# main.net
KiCad netlist of a schematic drawn in Altium Designer
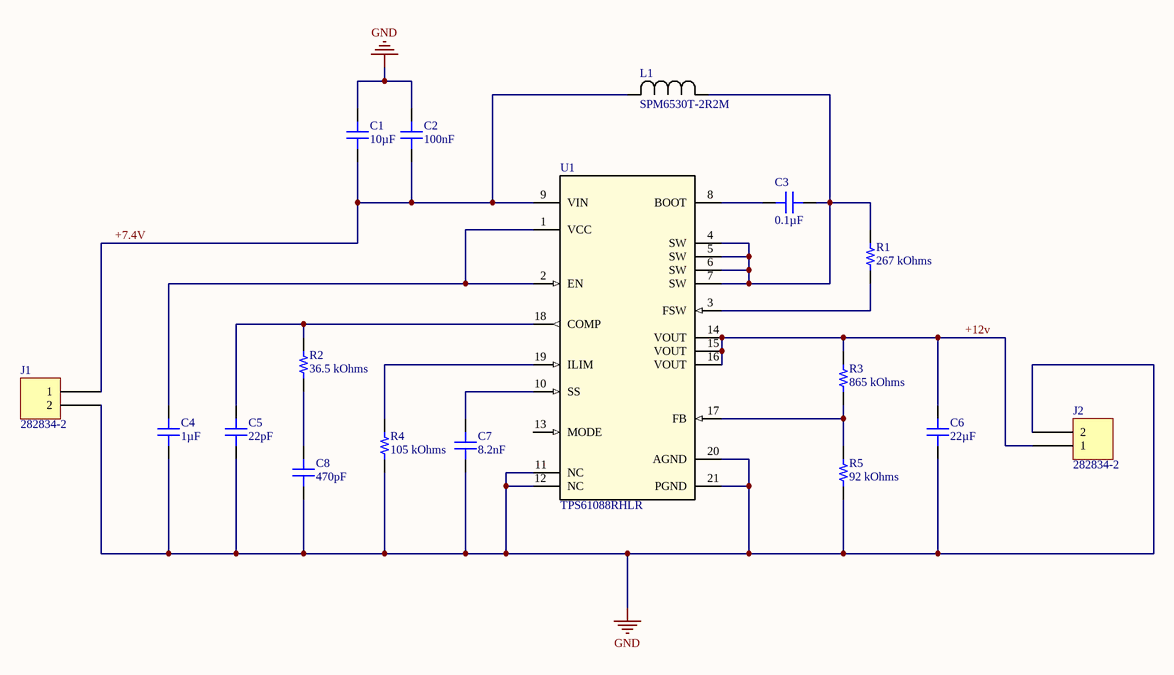
[diagram p0: main.SchDoc]

(export (version "E")
  (design (tool "Eeschema 10.0.6"))
  (components
    (comp (ref "C1")
      (value "10µF")
      (footprint "CAP 1210_3225 - 2.8MM")
      (description "CAP CER 10UF 50V X7S 1210")
      (fields
        (field (name "PART NUMBER") "GCJ32EC71H106KA01L")
        (field (name "MANUFACTURER") "Murata Electronics")
      )
      (libsource (lib "Celestial Altium Library - altium_library") (part "Capacitor"))
    )
    (comp (ref "C2")
      (value "100nF")
      (footprint "CAP 0603_1608")
      (description "CAP CER 22PF 25V C0G/NP0 0603")
      (fields (field (name "PART NUMBER") "06033A220KAT2A") (field (name "MANUFACTURER") "AVX Corporation"))
      (libsource (lib "Celestial Altium Library - altium_library") (part "Capacitor"))
    )
    (comp (ref "C3")
      (value "0.1µF")
      (footprint "CAP 0603_1608")
      (description "CAP CER 0.1UF 16V X7R 0603")
      (fields (field (name "PART NUMBER") "0603YC104JAT4A") (field (name "MANUFACTURER") "AVX Corporation"))
      (libsource (lib "Celestial Altium Library - altium_library") (part "Capacitor"))
    )
    (comp (ref "C4")
      (value "1µF")
      (footprint "CAP 0603_1608")
      (description "CAP CER 1UF 16V X5R 0603")
      (fields (field (name "PART NUMBER") "C0603C105K4PACTU") (field (name "MANUFACTURER") "KEMET"))
      (libsource (lib "Celestial Altium Library - altium_library") (part "Capacitor"))
    )
    (comp (ref "C5")
      (value "22pF")
      (footprint "CAP 0603_1608")
      (description "CAP CER 22PF 25V C0G/NP0 0603")
      (fields (field (name "PART NUMBER") "06033A220KAT2A") (field (name "MANUFACTURER") "AVX Corporation"))
      (libsource (lib "Celestial Altium Library - altium_library") (part "Capacitor"))
    )
    (comp (ref "C6")
      (value "22µF")
      (footprint "CAP 1210_3225 - 2.8MM")
      (description "CAP CER 22UF 25V X7R 1210")
      (fields
        (field (name "PART NUMBER") "GRM32ER71E226ME15K")
        (field (name "MANUFACTURER") "Murata Electronics")
      )
      (libsource (lib "Celestial Altium Library - altium_library") (part "Capacitor"))
    )
    (comp (ref "C7")
      (value "8.2nF")
      (footprint "CAP 0603_1608")
      (description "CAP CER 1UF 16V X5R 0603")
      (fields (field (name "PART NUMBER") "C0603C105K4PACTU") (field (name "MANUFACTURER") "KEMET"))
      (libsource (lib "Celestial Altium Library - altium_library") (part "Capacitor"))
    )
    (comp (ref "C8")
      (value "470pF")
      (footprint "CAP 0603_1608")
      (description "CAP CER 470PF 16V C0G/NP0 0603")
      (fields (field (name "PART NUMBER") "885012006027") (field (name "MANUFACTURER") "Würth Elektronik"))
      (libsource (lib "Celestial Altium Library - altium_library") (part "Capacitor"))
    )
    (comp (ref "J1")
      (value "282834-2")
      (footprint "TE 282834-2")
      (description "TERM BLK 2P SIDE ENT 2.54MM PCB")
      (fields (field (name "MANUFACTURER") "TE Connectivity AMP Connectors") (field (name "VOLTAGE") "150V"))
      (libsource (lib "Celestial Altium Library - altium_library") (part "2 Pin"))
    )
    (comp (ref "J2")
      (value "282834-2")
      (footprint "TE 282834-2")
      (description "TERM BLK 2P SIDE ENT 2.54MM PCB")
      (fields (field (name "MANUFACTURER") "TE Connectivity AMP Connectors") (field (name "VOLTAGE") "150V"))
      (libsource (lib "") (part "2 Pin_1"))
    )
    (comp (ref "L1")
      (value "SPM6530T-2R2M")
      (footprint "IND_SPM6530_TDK")
      (description "No Description Available")
      (fields (field (name "COPYRIGHT") "Copyright (C) 2018 Accelerated Designs. All rights reserved"))
      (libsource (lib "SPM6530T-2R2M") (part "SPM6530T-2R2M"))
    )
    (comp (ref "R1")
      (value "267 kOhms")
      (footprint "RES 0603_1608")
      (description "RES SMD 267K OHM 1% 1/10W 0603")
      (fields (field (name "PART NUMBER") "RC0603FR-07267KL") (field (name "MANUFACTURER") "Yageo"))
      (libsource (lib "Celestial Altium Library - altium_library") (part "Resistor"))
    )
    (comp (ref "R2")
      (value "36.5 kOhms")
      (footprint "RES 0603_1608")
      (description "RES SMD 36.5K OHM 1% 1/10W 0603")
      (fields (field (name "PART NUMBER") "CR0603-FX-3652ELF") (field (name "MANUFACTURER") "Bourns Inc."))
      (libsource (lib "Celestial Altium Library - altium_library") (part "Resistor"))
    )
    (comp (ref "R3")
      (value "865 kOhms")
      (footprint "RES 0603_1608")
      (description "RES SMD 267K OHM 1% 1/10W 0603")
      (fields (field (name "PART NUMBER") "RC0603FR-07267KL") (field (name "MANUFACTURER") "Yageo"))
      (libsource (lib "Celestial Altium Library - altium_library") (part "Resistor"))
    )
    (comp (ref "R4")
      (value "105 kOhms")
      (footprint "RES 0603_1608")
      (description "RES SMD 105K OHM 1% 1/10W 0603")
      (fields (field (name "PART NUMBER") "RC0603FR-07105KL") (field (name "MANUFACTURER") "Yageo"))
      (libsource (lib "Celestial Altium Library - altium_library") (part "Resistor"))
    )
    (comp (ref "R5")
      (value "92 kOhms")
      (footprint "RES 0805_2012")
      (description "RES SMD 392K OHM 0.1% 1/10W 0805")
      (fields
        (field (name "PART NUMBER") "RN73C2A392KBTDF")
        (field (name "MANUFACTURER") "TE Connectivity Passive Product")
      )
      (libsource (lib "Celestial Altium Library - altium_library") (part "Resistor"))
    )
    (comp (ref "U1")
      (value "TPS61088RHLR")
      (footprint "RHL0020A")
      (description "No Description Available")
      (fields
        (field (name "ALTERNATE_PARTNUMBER") "TPS61088RHLT")
        (field (name "MANUFACTURER") "Texas Instruments")
        (field (name "COPYRIGHT") "Copyright (C) 2018 Accelerated Designs. All rights reserved")
      )
      (libsource (lib "2021-01-31_10-50-26") (part "TPS61088RHLR"))
    )
  )
  (nets
    (net (code "1") (name "/+7.4V") (class "Default")
      (node (ref "C1") (pin "1") (pinfunction "1_1") (pintype "passive"))
      (node (ref "C2") (pin "1") (pinfunction "1_1") (pintype "passive"))
      (node (ref "J1") (pin "1") (pinfunction "1_1") (pintype "passive"))
      (node (ref "L1") (pin "2") (pinfunction "2_2") (pintype "passive"))
      (node (ref "U1") (pin "9") (pinfunction "VIN_9") (pintype "power_in"))
    )
    (net (code "2") (name "/+12v") (class "Default")
      (node (ref "C6") (pin "2") (pinfunction "2_2") (pintype "passive"))
      (node (ref "J2") (pin "1") (pinfunction "1_1") (pintype "passive"))
      (node (ref "R3") (pin "2") (pinfunction "2_2") (pintype "passive"))
      (node (ref "U1") (pin "14") (pinfunction "VOUT_14") (pintype "power_in"))
      (node (ref "U1") (pin "15") (pinfunction "VOUT_15") (pintype "power_in"))
      (node (ref "U1") (pin "16") (pinfunction "VOUT_16") (pintype "power_in"))
    )
    (net (code "3") (name "GND") (class "Default")
      (node (ref "C1") (pin "2") (pinfunction "2_2") (pintype "passive"))
      (node (ref "C2") (pin "2") (pinfunction "2_2") (pintype "passive"))
      (node (ref "C4") (pin "1") (pinfunction "1_1") (pintype "passive"))
      (node (ref "C5") (pin "1") (pinfunction "1_1") (pintype "passive"))
      (node (ref "C6") (pin "1") (pinfunction "1_1") (pintype "passive"))
      (node (ref "C7") (pin "1") (pinfunction "1_1") (pintype "passive"))
      (node (ref "C8") (pin "1") (pinfunction "1_1") (pintype "passive"))
      (node (ref "J1") (pin "2") (pinfunction "2_2") (pintype "passive"))
      (node (ref "J2") (pin "2") (pinfunction "2_2") (pintype "passive"))
      (node (ref "R4") (pin "1") (pinfunction "1_1") (pintype "passive"))
      (node (ref "R5") (pin "2") (pinfunction "2_2") (pintype "passive"))
      (node (ref "U1") (pin "11") (pinfunction "NC_11") (pintype "passive"))
      (node (ref "U1") (pin "12") (pinfunction "NC_12") (pintype "passive"))
      (node (ref "U1") (pin "20") (pinfunction "AGND_20") (pintype "power_in"))
      (node (ref "U1") (pin "21") (pinfunction "PGND_21") (pintype "power_in"))
    )
    (net (code "4") (name "Net-(C3-Pad2)") (class "Default")
      (node (ref "C3") (pin "2") (pinfunction "2_2") (pintype "passive"))
      (node (ref "L1") (pin "1") (pinfunction "1_1") (pintype "passive"))
      (node (ref "R1") (pin "2") (pinfunction "2_2") (pintype "passive"))
      (node (ref "U1") (pin "4") (pinfunction "SW_4") (pintype "power_in"))
      (node (ref "U1") (pin "5") (pinfunction "SW_5") (pintype "power_in"))
      (node (ref "U1") (pin "6") (pinfunction "SW_6") (pintype "power_in"))
      (node (ref "U1") (pin "7") (pinfunction "SW_7") (pintype "power_in"))
    )
    (net (code "5") (name "Net-(C8-Pad2)") (class "Default")
      (node (ref "C8") (pin "2") (pinfunction "2_2") (pintype "passive"))
      (node (ref "R2") (pin "1") (pinfunction "1_1") (pintype "passive"))
    )
    (net (code "6") (name "Net-(U1-BOOT)") (class "Default")
      (node (ref "C3") (pin "1") (pinfunction "1_1") (pintype "passive"))
      (node (ref "U1") (pin "8") (pinfunction "BOOT_8") (pintype "power_in"))
    )
    (net (code "7") (name "Net-(U1-COMP)") (class "Default")
      (node (ref "C5") (pin "2") (pinfunction "2_2") (pintype "passive"))
      (node (ref "R2") (pin "2") (pinfunction "2_2") (pintype "passive"))
      (node (ref "U1") (pin "18") (pinfunction "COMP_18") (pintype "output"))
    )
    (net (code "8") (name "Net-(U1-EN)") (class "Default")
      (node (ref "C4") (pin "2") (pinfunction "2_2") (pintype "passive"))
      (node (ref "U1") (pin "1") (pinfunction "VCC_1") (pintype "power_in"))
      (node (ref "U1") (pin "2") (pinfunction "EN_2") (pintype "input"))
    )
    (net (code "9") (name "Net-(U1-FB)") (class "Default")
      (node (ref "R3") (pin "1") (pinfunction "1_1") (pintype "passive"))
      (node (ref "R5") (pin "1") (pinfunction "1_1") (pintype "passive"))
      (node (ref "U1") (pin "17") (pinfunction "FB_17") (pintype "input"))
    )
    (net (code "10") (name "Net-(U1-FSW)") (class "Default")
      (node (ref "R1") (pin "1") (pinfunction "1_1") (pintype "passive"))
      (node (ref "U1") (pin "3") (pinfunction "FSW_3") (pintype "input"))
    )
    (net (code "11") (name "Net-(U1-ILIM)") (class "Default")
      (node (ref "R4") (pin "2") (pinfunction "2_2") (pintype "passive"))
      (node (ref "U1") (pin "19") (pinfunction "ILIM_19") (pintype "input"))
    )
    (net (code "12") (name "Net-(U1-SS)") (class "Default")
      (node (ref "C7") (pin "2") (pinfunction "2_2") (pintype "passive"))
      (node (ref "U1") (pin "10") (pinfunction "SS_10") (pintype "input"))
    )
    (net (code "13") (name "unconnected-(U1-MODE-Pad13)") (class "Default")
      (node (ref "U1") (pin "13") (pinfunction "MODE_13") (pintype "input"))
    )
  )
)
